# BLE_--_HM-10_--_Breakout_v0_9_8.net
KiCad netlist of a schematic drawn in EAGLE
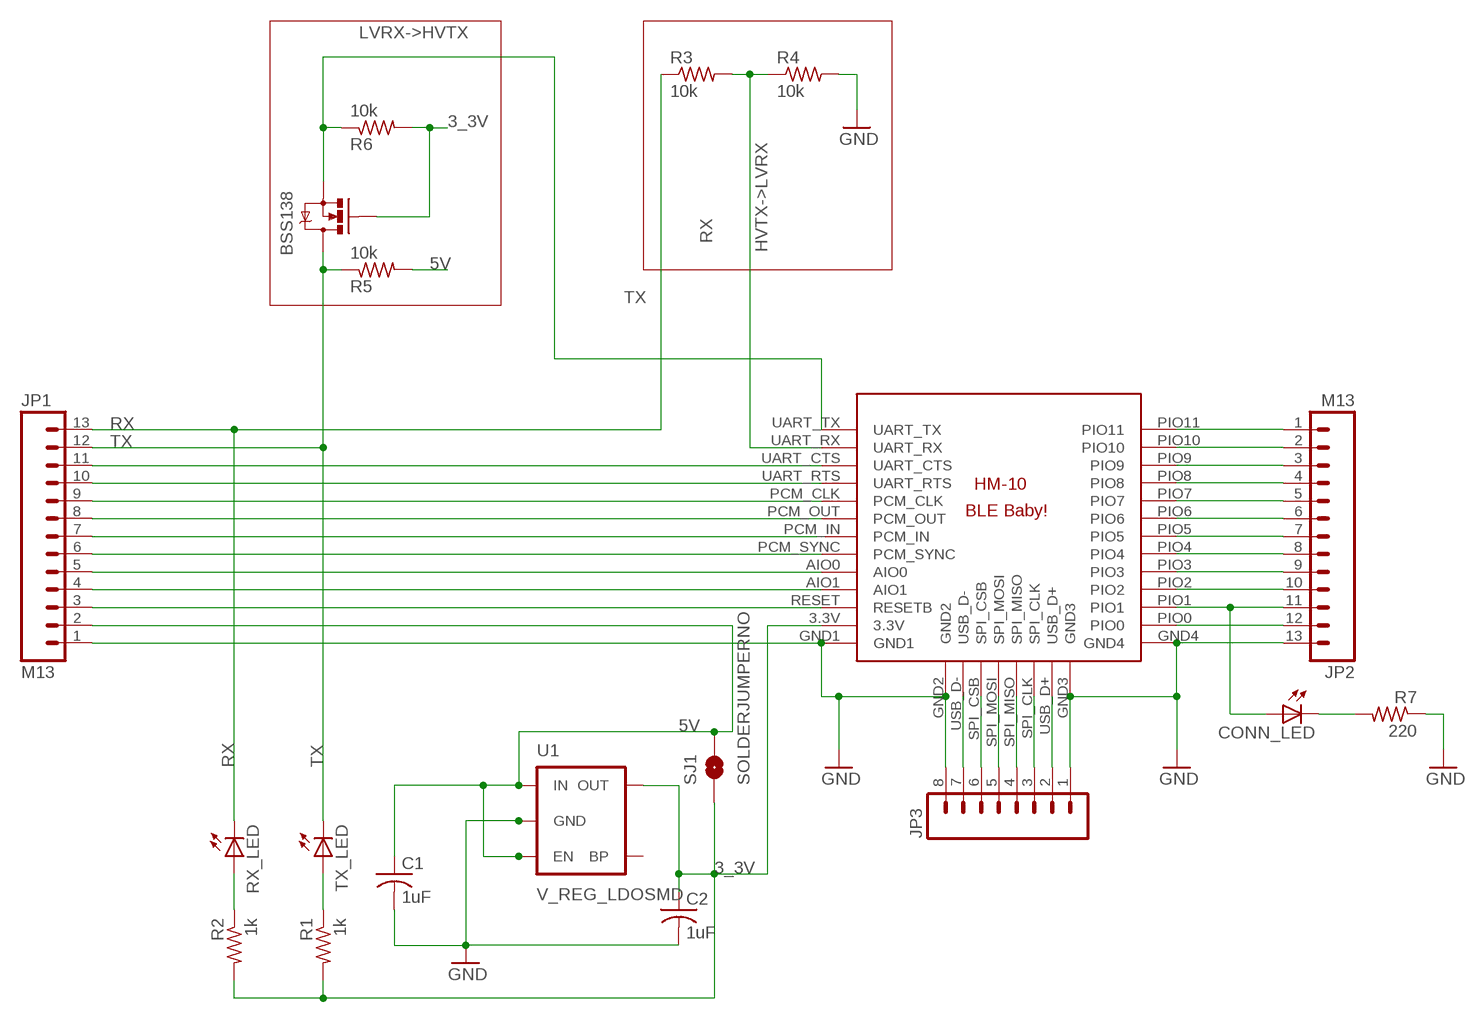
[diagram p0: schematic, sheet 1]

(export (version "E")
  (design (tool "Eeschema 10.0.6"))
  (components
    (comp (ref "BSS138")
      (value "MOSFET-NCHANNELSMD")
      (footprint "eagle-import:SOT23-3")
      (libsource (lib "eagle-import") (part "MOSFET-NCHANNELSMD"))
    )
    (comp (ref "C1")
      (value "1uF")
      (footprint "eagle-import:C0805K")
      (libsource (lib "eagle-import") (part "C-USC0805K"))
    )
    (comp (ref "C2")
      (value "1uF")
      (footprint "eagle-import:C0805K")
      (libsource (lib "eagle-import") (part "C-USC0805K"))
    )
    (comp (ref "CONN_LED")
      (value "LED0603")
      (footprint "eagle-import:LED-0603")
      (libsource (lib "eagle-import") (part "LED0603"))
    )
    (comp (ref "JP1")
      (value "M13")
      (footprint "eagle-import:1X13")
      (libsource (lib "eagle-import") (part "M13"))
    )
    (comp (ref "JP2")
      (value "M13")
      (footprint "eagle-import:1X13")
      (libsource (lib "eagle-import") (part "M13"))
    )
    (comp (ref "JP3")
      (value "M081X08")
      (footprint "eagle-import:1X08")
      (libsource (lib "eagle-import") (part "M081X08"))
    )
    (comp (ref "R1")
      (value "1k")
      (footprint "eagle-import:M0805")
      (libsource (lib "eagle-import") (part "R-US_M0805"))
    )
    (comp (ref "R2")
      (value "1k")
      (footprint "eagle-import:M0805")
      (libsource (lib "eagle-import") (part "R-US_M0805"))
    )
    (comp (ref "R3")
      (value "10k")
      (footprint "eagle-import:M0805")
      (libsource (lib "eagle-import") (part "R-US_M0805"))
    )
    (comp (ref "R4")
      (value "10k")
      (footprint "eagle-import:M0805")
      (libsource (lib "eagle-import") (part "R-US_M0805"))
    )
    (comp (ref "R5")
      (value "10k")
      (footprint "eagle-import:M0805")
      (libsource (lib "eagle-import") (part "R-US_M0805"))
    )
    (comp (ref "R6")
      (value "10k")
      (footprint "eagle-import:M0805")
      (libsource (lib "eagle-import") (part "R-US_M0805"))
    )
    (comp (ref "R7")
      (value "220")
      (footprint "eagle-import:M0805")
      (libsource (lib "eagle-import") (part "R-US_M0805"))
    )
    (comp (ref "RX_LED")
      (value "LED0603")
      (footprint "eagle-import:LED-0603")
      (libsource (lib "eagle-import") (part "LED0603"))
    )
    (comp (ref "SJ1")
      (value "SOLDERJUMPERNO")
      (footprint "eagle-import:SJ_2S-NO")
      (libsource (lib "eagle-import") (part "SOLDERJUMPERNO"))
    )
    (comp (ref "TX_LED")
      (value "LED0603")
      (footprint "eagle-import:LED-0603")
      (libsource (lib "eagle-import") (part "LED0603"))
    )
    (comp (ref "U$1")
      (value "BLE-HM-10")
      (footprint "eagle-import:BLE-HM-10")
      (libsource (lib "eagle-import") (part "BLE-HM-10"))
    )
    (comp (ref "U1")
      (value "V_REG_LDOSMD")
      (footprint "eagle-import:SOT23-5")
      (libsource (lib "eagle-import") (part "V_REG_LDOSMD"))
    )
  )
  (nets
    (net (code "1") (name "/3_3V") (class "Default")
      (node (ref "BSS138") (pin "1") (pinfunction "G_1") (pintype "passive"))
      (node (ref "C2") (pin "1") (pinfunction "1_1") (pintype "passive"))
      (node (ref "R1") (pin "2") (pinfunction "2_2") (pintype "passive"))
      (node (ref "R2") (pin "2") (pinfunction "2_2") (pintype "passive"))
      (node (ref "R6") (pin "2") (pinfunction "2_2") (pintype "passive"))
      (node (ref "SJ1") (pin "1") (pinfunction "1_1") (pintype "passive"))
      (node (ref "U$1") (pin "3.3V") (pinfunction "3.3V_3.3V") (pintype "bidirectional"))
      (node (ref "U1") (pin "5") (pinfunction "OUT_5") (pintype "passive"))
    )
    (net (code "2") (name "/5V") (class "Default")
      (node (ref "C1") (pin "1") (pinfunction "1_1") (pintype "passive"))
      (node (ref "JP1") (pin "2") (pinfunction "2_2") (pintype "passive"))
      (node (ref "R5") (pin "2") (pinfunction "2_2") (pintype "passive"))
      (node (ref "SJ1") (pin "2") (pinfunction "2_2") (pintype "passive"))
      (node (ref "U1") (pin "1") (pinfunction "IN_1") (pintype "input"))
      (node (ref "U1") (pin "3") (pinfunction "EN_3") (pintype "input"))
    )
    (net (code "3") (name "/HVTX->LVRX") (class "Default")
      (node (ref "R3") (pin "2") (pinfunction "2_2") (pintype "passive"))
      (node (ref "R4") (pin "1") (pinfunction "1_1") (pintype "passive"))
      (node (ref "U$1") (pin "UART_RX") (pinfunction "UART_RX_UART_RX") (pintype "bidirectional"))
    )
    (net (code "4") (name "/LVRX->HVTX") (class "Default")
      (node (ref "BSS138") (pin "2") (pinfunction "S_2") (pintype "passive"))
      (node (ref "R6") (pin "1") (pinfunction "1_1") (pintype "passive"))
      (node (ref "U$1") (pin "UART_TX") (pinfunction "UART_TX_UART_TX") (pintype "bidirectional"))
    )
    (net (code "5") (name "/RX") (class "Default")
      (node (ref "JP1") (pin "13") (pinfunction "13_13") (pintype "passive"))
      (node (ref "R3") (pin "1") (pinfunction "1_1") (pintype "passive"))
      (node (ref "RX_LED") (pin "C") (pinfunction "C_C") (pintype "passive"))
    )
    (net (code "6") (name "/TX") (class "Default")
      (node (ref "BSS138") (pin "3") (pinfunction "D_3") (pintype "passive"))
      (node (ref "JP1") (pin "12") (pinfunction "12_12") (pintype "passive"))
      (node (ref "R5") (pin "1") (pinfunction "1_1") (pintype "passive"))
      (node (ref "TX_LED") (pin "C") (pinfunction "C_C") (pintype "passive"))
    )
    (net (code "7") (name "GND") (class "Default")
      (node (ref "C1") (pin "2") (pinfunction "2_2") (pintype "passive"))
      (node (ref "C2") (pin "2") (pinfunction "2_2") (pintype "passive"))
      (node (ref "JP1") (pin "1") (pinfunction "1_1") (pintype "passive"))
      (node (ref "JP2") (pin "13") (pinfunction "13_13") (pintype "passive"))
      (node (ref "JP3") (pin "1") (pinfunction "1_1") (pintype "passive"))
      (node (ref "JP3") (pin "8") (pinfunction "8_8") (pintype "passive"))
      (node (ref "R4") (pin "2") (pinfunction "2_2") (pintype "passive"))
      (node (ref "R7") (pin "1") (pinfunction "1_1") (pintype "passive"))
      (node (ref "U$1") (pin "GND1") (pinfunction "GND1_GND1") (pintype "bidirectional"))
      (node (ref "U$1") (pin "GND2") (pinfunction "GND2_GND2") (pintype "bidirectional"))
      (node (ref "U$1") (pin "GND3") (pinfunction "GND3_GND3") (pintype "bidirectional"))
      (node (ref "U$1") (pin "GND4") (pinfunction "GND4_GND4") (pintype "bidirectional"))
      (node (ref "U1") (pin "2") (pinfunction "GND_2") (pintype "input"))
    )
    (net (code "8") (name "Net-(CONN_LED-PadA)") (class "Default")
      (node (ref "CONN_LED") (pin "A") (pinfunction "A_A") (pintype "passive"))
      (node (ref "JP2") (pin "11") (pinfunction "11_11") (pintype "passive"))
      (node (ref "U$1") (pin "PIO1") (pinfunction "PIO1_PIO1") (pintype "bidirectional"))
    )
    (net (code "9") (name "Net-(CONN_LED-PadC)") (class "Default")
      (node (ref "CONN_LED") (pin "C") (pinfunction "C_C") (pintype "passive"))
      (node (ref "R7") (pin "2") (pinfunction "2_2") (pintype "passive"))
    )
    (net (code "10") (name "Net-(JP1-Pad4)") (class "Default")
      (node (ref "JP1") (pin "4") (pinfunction "4_4") (pintype "passive"))
      (node (ref "U$1") (pin "AIO1") (pinfunction "AIO1_AIO1") (pintype "bidirectional"))
    )
    (net (code "11") (name "Net-(JP1-Pad5)") (class "Default")
      (node (ref "JP1") (pin "5") (pinfunction "5_5") (pintype "passive"))
      (node (ref "U$1") (pin "AIO0") (pinfunction "AIO0_AIO0") (pintype "bidirectional"))
    )
    (net (code "12") (name "Net-(JP1-Pad6)") (class "Default")
      (node (ref "JP1") (pin "6") (pinfunction "6_6") (pintype "passive"))
      (node (ref "U$1") (pin "PCM_SYNC") (pinfunction "PCM_SYNC_PCM_SYNC") (pintype "bidirectional"))
    )
    (net (code "13") (name "Net-(JP1-Pad7)") (class "Default")
      (node (ref "JP1") (pin "7") (pinfunction "7_7") (pintype "passive"))
      (node (ref "U$1") (pin "PCM_IN") (pinfunction "PCM_IN_PCM_IN") (pintype "bidirectional"))
    )
    (net (code "14") (name "Net-(JP1-Pad8)") (class "Default")
      (node (ref "JP1") (pin "8") (pinfunction "8_8") (pintype "passive"))
      (node (ref "U$1") (pin "PCM_OUT") (pinfunction "PCM_OUT_PCM_OUT") (pintype "bidirectional"))
    )
    (net (code "15") (name "Net-(JP1-Pad9)") (class "Default")
      (node (ref "JP1") (pin "9") (pinfunction "9_9") (pintype "passive"))
      (node (ref "U$1") (pin "PCM_CLK") (pinfunction "PCM_CLK_PCM_CLK") (pintype "bidirectional"))
    )
    (net (code "16") (name "Net-(JP1-Pad10)") (class "Default")
      (node (ref "JP1") (pin "10") (pinfunction "10_10") (pintype "passive"))
      (node (ref "U$1") (pin "UART_RTS") (pinfunction "UART_RTS_UART_RTS") (pintype "bidirectional"))
    )
    (net (code "17") (name "Net-(JP1-Pad11)") (class "Default")
      (node (ref "JP1") (pin "11") (pinfunction "11_11") (pintype "passive"))
      (node (ref "U$1") (pin "UART_CTS") (pinfunction "UART_CTS_UART_CTS") (pintype "bidirectional"))
    )
    (net (code "18") (name "Net-(JP2-Pad1)") (class "Default")
      (node (ref "JP2") (pin "1") (pinfunction "1_1") (pintype "passive"))
      (node (ref "U$1") (pin "PIO11") (pinfunction "PIO11_PIO11") (pintype "bidirectional"))
    )
    (net (code "19") (name "Net-(JP2-Pad2)") (class "Default")
      (node (ref "JP2") (pin "2") (pinfunction "2_2") (pintype "passive"))
      (node (ref "U$1") (pin "PIO10") (pinfunction "PIO10_PIO10") (pintype "bidirectional"))
    )
    (net (code "20") (name "Net-(JP2-Pad3)") (class "Default")
      (node (ref "JP2") (pin "3") (pinfunction "3_3") (pintype "passive"))
      (node (ref "U$1") (pin "PIO9") (pinfunction "PIO9_PIO9") (pintype "bidirectional"))
    )
    (net (code "21") (name "Net-(JP2-Pad4)") (class "Default")
      (node (ref "JP2") (pin "4") (pinfunction "4_4") (pintype "passive"))
      (node (ref "U$1") (pin "PIO8") (pinfunction "PIO8_PIO8") (pintype "bidirectional"))
    )
    (net (code "22") (name "Net-(JP2-Pad5)") (class "Default")
      (node (ref "JP2") (pin "5") (pinfunction "5_5") (pintype "passive"))
      (node (ref "U$1") (pin "PIO7") (pinfunction "PIO7_PIO7") (pintype "bidirectional"))
    )
    (net (code "23") (name "Net-(JP2-Pad6)") (class "Default")
      (node (ref "JP2") (pin "6") (pinfunction "6_6") (pintype "passive"))
      (node (ref "U$1") (pin "PIO6") (pinfunction "PIO6_PIO6") (pintype "bidirectional"))
    )
    (net (code "24") (name "Net-(JP2-Pad7)") (class "Default")
      (node (ref "JP2") (pin "7") (pinfunction "7_7") (pintype "passive"))
      (node (ref "U$1") (pin "PIO5") (pinfunction "PIO5_PIO5") (pintype "bidirectional"))
    )
    (net (code "25") (name "Net-(JP2-Pad8)") (class "Default")
      (node (ref "JP2") (pin "8") (pinfunction "8_8") (pintype "passive"))
      (node (ref "U$1") (pin "PIO4") (pinfunction "PIO4_PIO4") (pintype "bidirectional"))
    )
    (net (code "26") (name "Net-(JP2-Pad9)") (class "Default")
      (node (ref "JP2") (pin "9") (pinfunction "9_9") (pintype "passive"))
      (node (ref "U$1") (pin "PIO3") (pinfunction "PIO3_PIO3") (pintype "bidirectional"))
    )
    (net (code "27") (name "Net-(JP2-Pad10)") (class "Default")
      (node (ref "JP2") (pin "10") (pinfunction "10_10") (pintype "passive"))
      (node (ref "U$1") (pin "PIO2") (pinfunction "PIO2_PIO2") (pintype "bidirectional"))
    )
    (net (code "28") (name "Net-(JP2-Pad12)") (class "Default")
      (node (ref "JP2") (pin "12") (pinfunction "12_12") (pintype "passive"))
      (node (ref "U$1") (pin "PIO0") (pinfunction "PIO0_PIO0") (pintype "bidirectional"))
    )
    (net (code "29") (name "Net-(JP3-Pad2)") (class "Default")
      (node (ref "JP3") (pin "2") (pinfunction "2_2") (pintype "passive"))
      (node (ref "U$1") (pin "USB_D+") (pinfunction "USB_D+_USB_D+") (pintype "bidirectional"))
    )
    (net (code "30") (name "Net-(JP3-Pad3)") (class "Default")
      (node (ref "JP3") (pin "3") (pinfunction "3_3") (pintype "passive"))
      (node (ref "U$1") (pin "SPI_CLK") (pinfunction "SPI_CLK_SPI_CLK") (pintype "bidirectional"))
    )
    (net (code "31") (name "Net-(JP3-Pad4)") (class "Default")
      (node (ref "JP3") (pin "4") (pinfunction "4_4") (pintype "passive"))
      (node (ref "U$1") (pin "SPI_MISO") (pinfunction "SPI_MISO_SPI_MISO") (pintype "bidirectional"))
    )
    (net (code "32") (name "Net-(JP3-Pad5)") (class "Default")
      (node (ref "JP3") (pin "5") (pinfunction "5_5") (pintype "passive"))
      (node (ref "U$1") (pin "SPI_MOSI") (pinfunction "SPI_MOSI_SPI_MOSI") (pintype "bidirectional"))
    )
    (net (code "33") (name "Net-(JP3-Pad6)") (class "Default")
      (node (ref "JP3") (pin "6") (pinfunction "6_6") (pintype "passive"))
      (node (ref "U$1") (pin "SPI_CSB") (pinfunction "SPI_CSB_SPI_CSB") (pintype "bidirectional"))
    )
    (net (code "34") (name "Net-(JP3-Pad7)") (class "Default")
      (node (ref "JP3") (pin "7") (pinfunction "7_7") (pintype "passive"))
      (node (ref "U$1") (pin "USB_D-") (pinfunction "USB_D-_USB_D-") (pintype "bidirectional"))
    )
    (net (code "35") (name "Net-(R1-Pad1)") (class "Default")
      (node (ref "R1") (pin "1") (pinfunction "1_1") (pintype "passive"))
      (node (ref "TX_LED") (pin "A") (pinfunction "A_A") (pintype "passive"))
    )
    (net (code "36") (name "Net-(R2-Pad1)") (class "Default")
      (node (ref "R2") (pin "1") (pinfunction "1_1") (pintype "passive"))
      (node (ref "RX_LED") (pin "A") (pinfunction "A_A") (pintype "passive"))
    )
    (net (code "37") (name "Net-(U$1-RESETB)") (class "Default")
      (node (ref "JP1") (pin "3") (pinfunction "3_3") (pintype "passive"))
      (node (ref "U$1") (pin "RESET") (pinfunction "RESETB_RESET") (pintype "bidirectional"))
    )
    (net (code "38") (name "unconnected-(U1-BP-Pad4)") (class "Default")
      (node (ref "U1") (pin "4") (pinfunction "BP_4") (pintype "input"))
    )
  )
)
